# S01-INTERFACES.net
KiCad netlist of a schematic drawn in Altium Designer
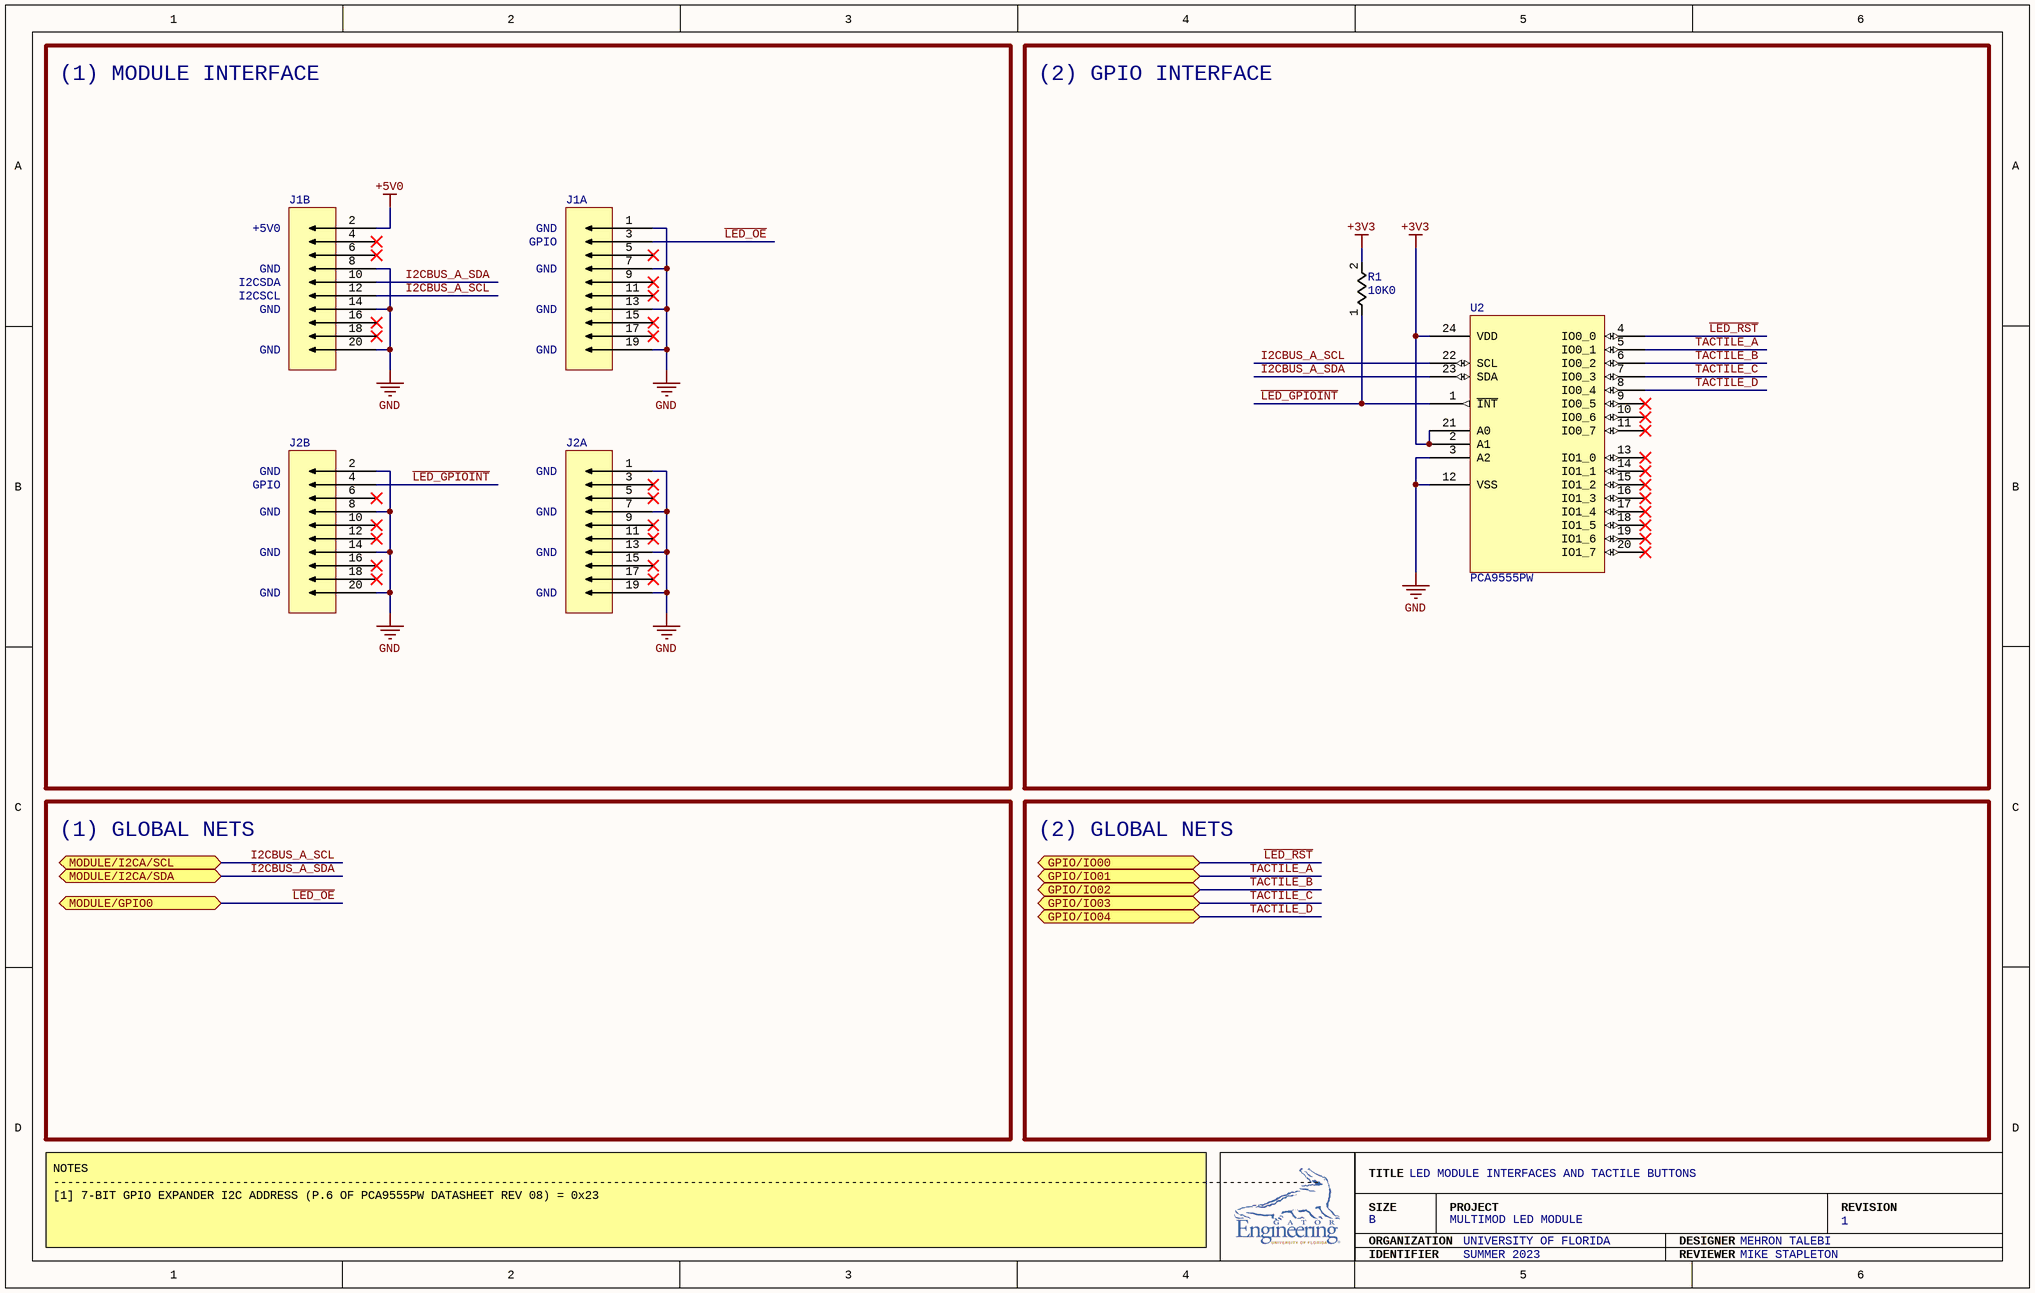
[diagram p0: S01-INTERFACES.SchDoc]

(export (version "E")
  (design (tool "Eeschema 10.0.6"))
  (components
    (comp (ref "J1")
      (value "NPTC102KFMS-RC")
      (footprint "NPTC102KFMS-RC")
      (description "CONN HDR 20POS 0.1 TIN SMD")
      (libsource (lib "Master") (part "NPTC102KFMS-RC"))
    )
    (comp (ref "J2")
      (value "NPTC102KFMS-RC")
      (footprint "NPTC102KFMS-RC")
      (description "CONN HDR 20POS 0.1 TIN SMD")
      (libsource (lib "Master") (part "NPTC102KFMS-RC"))
    )
    (comp (ref "R1")
      (value "10K0")
      (footprint "RC0805FR-0710KL")
      (description "RES 10K OHM 1% 1/8W 0805")
      (fields (field (name "TOLERANCE") "±1%"))
      (libsource (lib "Master") (part "RC0805FR-0710KL"))
    )
    (comp (ref "U2")
      (value "PCA9555PW")
      (footprint "PCA9555PW")
      (description "IC XPND 400KHZ I2C SMBUS 24TSSOP")
      (libsource (lib "Master") (part "PCA9555PW"))
    )
  )
  (nets
    (net (code "1") (name "+3V3") (class "Default")
      (node (ref "R1") (pin "2") (pinfunction "2_2") (pintype "passive"))
      (node (ref "U2") (pin "2") (pinfunction "A1_2") (pintype "passive"))
      (node (ref "U2") (pin "21") (pinfunction "A0_21") (pintype "passive"))
      (node (ref "U2") (pin "24") (pinfunction "VDD_24") (pintype "power_in"))
    )
    (net (code "2") (name "+5V0") (class "Default")
      (node (ref "J1") (pin "2") (pinfunction "2_2") (pintype "passive"))
    )
    (net (code "3") (name "/I2CBUS_A_SCL") (class "Default")
      (node (ref "J1") (pin "12") (pinfunction "12_12") (pintype "passive"))
      (node (ref "U2") (pin "22") (pinfunction "SCL_22") (pintype "bidirectional"))
    )
    (net (code "4") (name "/I2CBUS_A_SDA") (class "Default")
      (node (ref "J1") (pin "10") (pinfunction "10_10") (pintype "passive"))
      (node (ref "U2") (pin "23") (pinfunction "SDA_23") (pintype "bidirectional"))
    )
    (net (code "5") (name "/LED_GPIOINT") (class "Default")
      (node (ref "J2") (pin "4") (pinfunction "4_4") (pintype "passive"))
      (node (ref "R1") (pin "1") (pinfunction "1_1") (pintype "passive"))
      (node (ref "U2") (pin "1") (pinfunction "INT_1") (pintype "output"))
    )
    (net (code "6") (name "/LED_OE") (class "Default")
      (node (ref "J1") (pin "3") (pinfunction "3_3") (pintype "passive"))
    )
    (net (code "7") (name "/LED_RST") (class "Default")
      (node (ref "U2") (pin "4") (pinfunction "IO0_0_4") (pintype "bidirectional"))
    )
    (net (code "8") (name "/TACTILE_A") (class "Default")
      (node (ref "U2") (pin "5") (pinfunction "IO0_1_5") (pintype "bidirectional"))
    )
    (net (code "9") (name "/TACTILE_B") (class "Default")
      (node (ref "U2") (pin "6") (pinfunction "IO0_2_6") (pintype "bidirectional"))
    )
    (net (code "10") (name "/TACTILE_C") (class "Default")
      (node (ref "U2") (pin "7") (pinfunction "IO0_3_7") (pintype "bidirectional"))
    )
    (net (code "11") (name "/TACTILE_D") (class "Default")
      (node (ref "U2") (pin "8") (pinfunction "IO0_4_8") (pintype "bidirectional"))
    )
    (net (code "12") (name "GND") (class "Default")
      (node (ref "J1") (pin "1") (pinfunction "1_1") (pintype "passive"))
      (node (ref "J1") (pin "13") (pinfunction "13_13") (pintype "passive"))
      (node (ref "J1") (pin "14") (pinfunction "14_14") (pintype "passive"))
      (node (ref "J1") (pin "19") (pinfunction "19_19") (pintype "passive"))
      (node (ref "J1") (pin "20") (pinfunction "20_20") (pintype "passive"))
      (node (ref "J1") (pin "7") (pinfunction "7_7") (pintype "passive"))
      (node (ref "J1") (pin "8") (pinfunction "8_8") (pintype "passive"))
      (node (ref "J2") (pin "1") (pinfunction "1_1") (pintype "passive"))
      (node (ref "J2") (pin "13") (pinfunction "13_13") (pintype "passive"))
      (node (ref "J2") (pin "14") (pinfunction "14_14") (pintype "passive"))
      (node (ref "J2") (pin "19") (pinfunction "19_19") (pintype "passive"))
      (node (ref "J2") (pin "2") (pinfunction "2_2") (pintype "passive"))
      (node (ref "J2") (pin "20") (pinfunction "20_20") (pintype "passive"))
      (node (ref "J2") (pin "7") (pinfunction "7_7") (pintype "passive"))
      (node (ref "J2") (pin "8") (pinfunction "8_8") (pintype "passive"))
      (node (ref "U2") (pin "12") (pinfunction "VSS_12") (pintype "power_in"))
      (node (ref "U2") (pin "3") (pinfunction "A2_3") (pintype "passive"))
    )
    (net (code "13") (name "unconnected-(J1-Pad4)") (class "Default")
      (node (ref "J1") (pin "4") (pinfunction "4_4") (pintype "passive+no_connect"))
    )
    (net (code "14") (name "unconnected-(J1-Pad5)") (class "Default")
      (node (ref "J1") (pin "5") (pinfunction "5_5") (pintype "passive+no_connect"))
    )
    (net (code "15") (name "unconnected-(J1-Pad6)") (class "Default")
      (node (ref "J1") (pin "6") (pinfunction "6_6") (pintype "passive+no_connect"))
    )
    (net (code "16") (name "unconnected-(J1-Pad9)") (class "Default")
      (node (ref "J1") (pin "9") (pinfunction "9_9") (pintype "passive+no_connect"))
    )
    (net (code "17") (name "unconnected-(J1-Pad11)") (class "Default")
      (node (ref "J1") (pin "11") (pinfunction "11_11") (pintype "passive+no_connect"))
    )
    (net (code "18") (name "unconnected-(J1-Pad15)") (class "Default")
      (node (ref "J1") (pin "15") (pinfunction "15_15") (pintype "passive+no_connect"))
    )
    (net (code "19") (name "unconnected-(J1-Pad16)") (class "Default")
      (node (ref "J1") (pin "16") (pinfunction "16_16") (pintype "passive+no_connect"))
    )
    (net (code "20") (name "unconnected-(J1-Pad17)") (class "Default")
      (node (ref "J1") (pin "17") (pinfunction "17_17") (pintype "passive+no_connect"))
    )
    (net (code "21") (name "unconnected-(J1-Pad18)") (class "Default")
      (node (ref "J1") (pin "18") (pinfunction "18_18") (pintype "passive+no_connect"))
    )
    (net (code "22") (name "unconnected-(J2-Pad3)") (class "Default")
      (node (ref "J2") (pin "3") (pinfunction "3_3") (pintype "passive+no_connect"))
    )
    (net (code "23") (name "unconnected-(J2-Pad5)") (class "Default")
      (node (ref "J2") (pin "5") (pinfunction "5_5") (pintype "passive+no_connect"))
    )
    (net (code "24") (name "unconnected-(J2-Pad6)") (class "Default")
      (node (ref "J2") (pin "6") (pinfunction "6_6") (pintype "passive+no_connect"))
    )
    (net (code "25") (name "unconnected-(J2-Pad9)") (class "Default")
      (node (ref "J2") (pin "9") (pinfunction "9_9") (pintype "passive+no_connect"))
    )
    (net (code "26") (name "unconnected-(J2-Pad10)") (class "Default")
      (node (ref "J2") (pin "10") (pinfunction "10_10") (pintype "passive+no_connect"))
    )
    (net (code "27") (name "unconnected-(J2-Pad11)") (class "Default")
      (node (ref "J2") (pin "11") (pinfunction "11_11") (pintype "passive+no_connect"))
    )
    (net (code "28") (name "unconnected-(J2-Pad12)") (class "Default")
      (node (ref "J2") (pin "12") (pinfunction "12_12") (pintype "passive+no_connect"))
    )
    (net (code "29") (name "unconnected-(J2-Pad15)") (class "Default")
      (node (ref "J2") (pin "15") (pinfunction "15_15") (pintype "passive+no_connect"))
    )
    (net (code "30") (name "unconnected-(J2-Pad16)") (class "Default")
      (node (ref "J2") (pin "16") (pinfunction "16_16") (pintype "passive+no_connect"))
    )
    (net (code "31") (name "unconnected-(J2-Pad17)") (class "Default")
      (node (ref "J2") (pin "17") (pinfunction "17_17") (pintype "passive+no_connect"))
    )
    (net (code "32") (name "unconnected-(J2-Pad18)") (class "Default")
      (node (ref "J2") (pin "18") (pinfunction "18_18") (pintype "passive+no_connect"))
    )
    (net (code "33") (name "unconnected-(U2-IO0_5-Pad9)") (class "Default")
      (node (ref "U2") (pin "9") (pinfunction "IO0_5_9") (pintype "bidirectional+no_connect"))
    )
    (net (code "34") (name "unconnected-(U2-IO0_6-Pad10)") (class "Default")
      (node (ref "U2") (pin "10") (pinfunction "IO0_6_10") (pintype "bidirectional+no_connect"))
    )
    (net (code "35") (name "unconnected-(U2-IO0_7-Pad11)") (class "Default")
      (node (ref "U2") (pin "11") (pinfunction "IO0_7_11") (pintype "bidirectional+no_connect"))
    )
    (net (code "36") (name "unconnected-(U2-IO1_0-Pad13)") (class "Default")
      (node (ref "U2") (pin "13") (pinfunction "IO1_0_13") (pintype "bidirectional+no_connect"))
    )
    (net (code "37") (name "unconnected-(U2-IO1_1-Pad14)") (class "Default")
      (node (ref "U2") (pin "14") (pinfunction "IO1_1_14") (pintype "bidirectional+no_connect"))
    )
    (net (code "38") (name "unconnected-(U2-IO1_2-Pad15)") (class "Default")
      (node (ref "U2") (pin "15") (pinfunction "IO1_2_15") (pintype "bidirectional+no_connect"))
    )
    (net (code "39") (name "unconnected-(U2-IO1_3-Pad16)") (class "Default")
      (node (ref "U2") (pin "16") (pinfunction "IO1_3_16") (pintype "bidirectional+no_connect"))
    )
    (net (code "40") (name "unconnected-(U2-IO1_4-Pad17)") (class "Default")
      (node (ref "U2") (pin "17") (pinfunction "IO1_4_17") (pintype "bidirectional+no_connect"))
    )
    (net (code "41") (name "unconnected-(U2-IO1_5-Pad18)") (class "Default")
      (node (ref "U2") (pin "18") (pinfunction "IO1_5_18") (pintype "bidirectional+no_connect"))
    )
    (net (code "42") (name "unconnected-(U2-IO1_6-Pad19)") (class "Default")
      (node (ref "U2") (pin "19") (pinfunction "IO1_6_19") (pintype "bidirectional+no_connect"))
    )
    (net (code "43") (name "unconnected-(U2-IO1_7-Pad20)") (class "Default")
      (node (ref "U2") (pin "20") (pinfunction "IO1_7_20") (pintype "bidirectional+no_connect"))
    )
  )
)
